# ps2_atmega32__board_with_connector_shogi.net
KiCad netlist of a schematic drawn in EAGLE
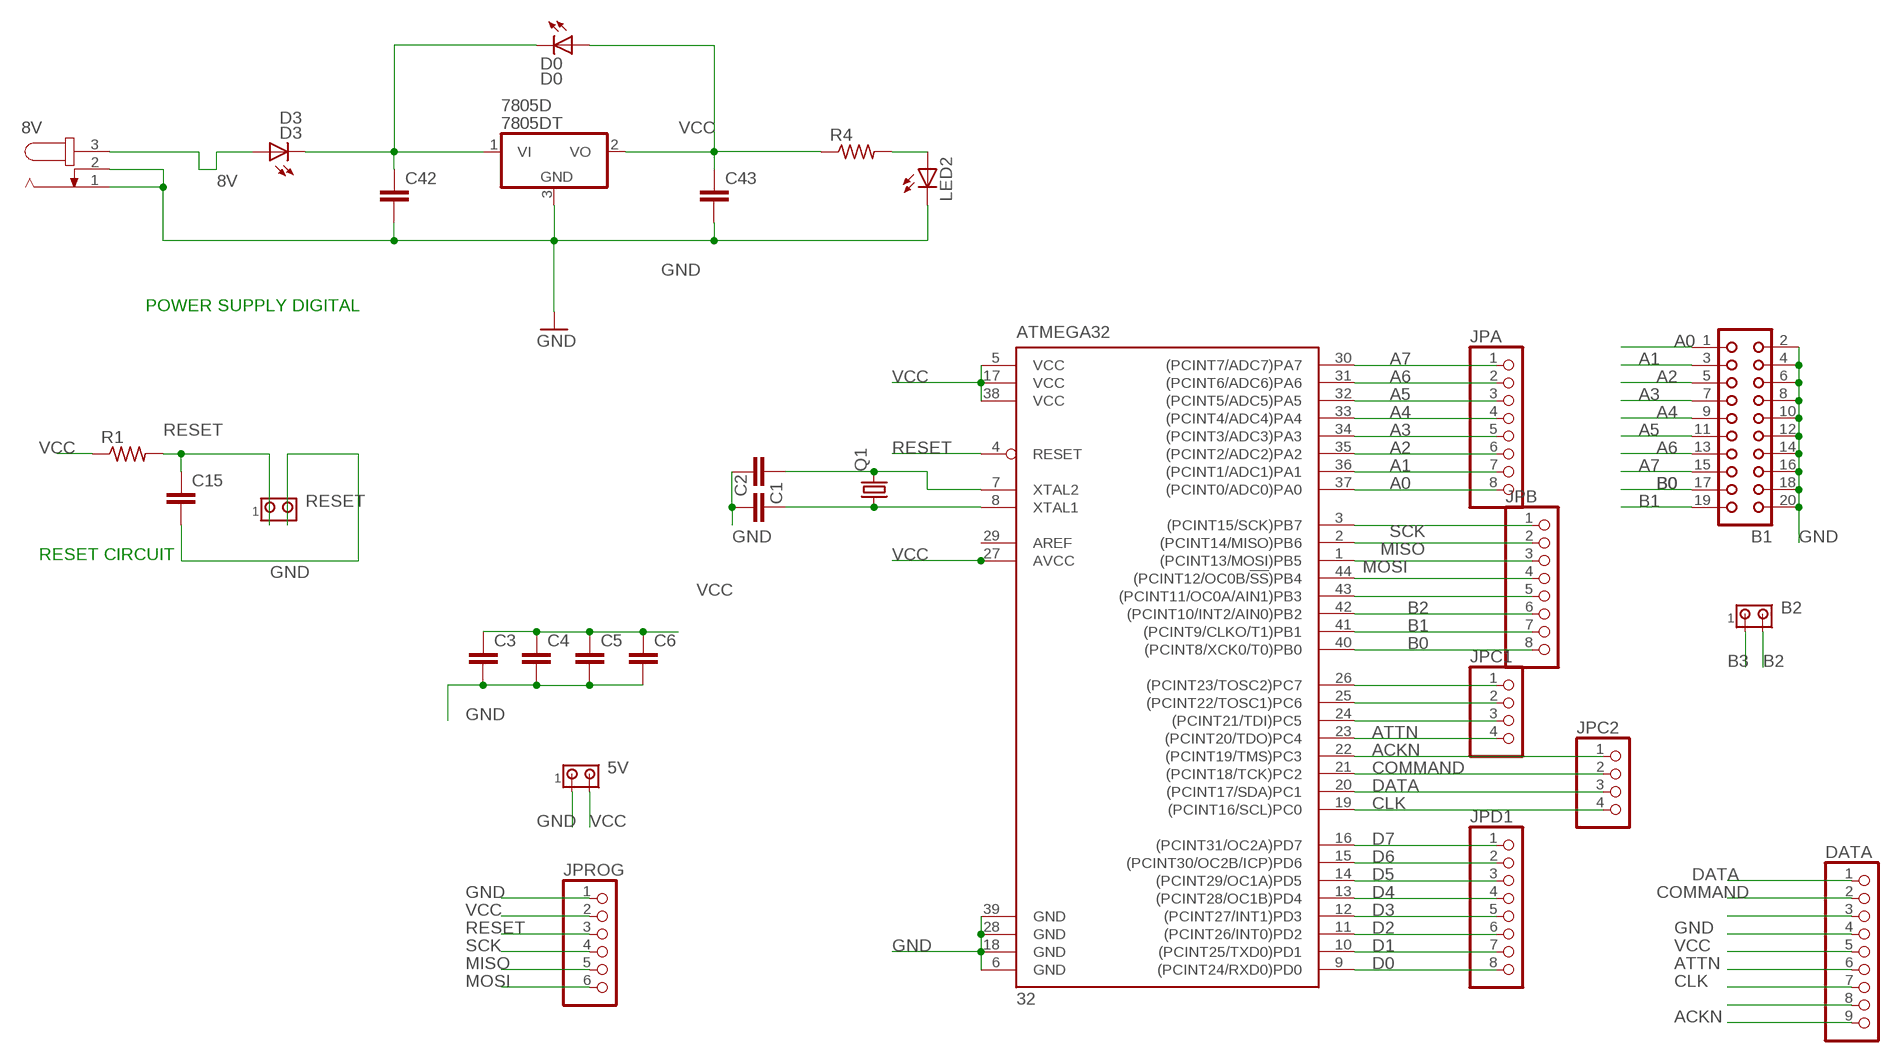
[diagram p0: schematic, sheet 1]

(export (version "E")
  (design (tool "Eeschema 10.0.6"))
  (components
    (comp (ref "5V")
      (value "MTA02-100")
      (footprint "eagle-import:10X02MTA")
      (libsource (lib "eagle-import") (part "MTA02-100"))
    )
    (comp (ref "8V")
      (value "JACK-PLUG0")
      (footprint "eagle-import:SPC4077")
      (libsource (lib "eagle-import") (part "JACK-PLUG0"))
    )
    (comp (ref "7805D")
      (value "7805DT")
      (footprint "eagle-import:TO252")
      (libsource (lib "eagle-import") (part "78DT05"))
    )
    (comp (ref "ATMEGA32")
      (value "32")
      (footprint "eagle-import:TQFP44")
      (libsource (lib "eagle-import") (part "ATMEGA644A"))
    )
    (comp (ref "B1")
      (value "CON20L")
      (footprint "eagle-import:CON20L")
      (libsource (lib "eagle-import") (part "CON20L"))
    )
    (comp (ref "B2")
      (value "MTA02-100")
      (footprint "eagle-import:10X02MTA")
      (libsource (lib "eagle-import") (part "MTA02-100"))
    )
    (comp (ref "C1")
      (value "C-EUC0603K")
      (footprint "eagle-import:C0603K")
      (libsource (lib "eagle-import") (part "C-EUC0603K"))
    )
    (comp (ref "C2")
      (value "C-EUC0603K")
      (footprint "eagle-import:C0603K")
      (libsource (lib "eagle-import") (part "C-EUC0603K"))
    )
    (comp (ref "C3")
      (value "C-EUC0603K")
      (footprint "eagle-import:C0603K")
      (libsource (lib "eagle-import") (part "C-EUC0603K"))
    )
    (comp (ref "C4")
      (value "C-EUC0603K")
      (footprint "eagle-import:C0603K")
      (libsource (lib "eagle-import") (part "C-EUC0603K"))
    )
    (comp (ref "C5")
      (value "C-EUC0603K")
      (footprint "eagle-import:C0603K")
      (libsource (lib "eagle-import") (part "C-EUC0603K"))
    )
    (comp (ref "C6")
      (value "C-EUC0603K")
      (footprint "eagle-import:C0603K")
      (libsource (lib "eagle-import") (part "C-EUC0603K"))
    )
    (comp (ref "C15")
      (value "C-EUC0603")
      (footprint "eagle-import:C0603")
      (libsource (lib "eagle-import") (part "C-EUC0603"))
    )
    (comp (ref "C42")
      (value "C-EUC0603")
      (footprint "eagle-import:C0603")
      (libsource (lib "eagle-import") (part "C-EUC0603"))
    )
    (comp (ref "C43")
      (value "C-EUC0603")
      (footprint "eagle-import:C0603")
      (libsource (lib "eagle-import") (part "C-EUC0603"))
    )
    (comp (ref "D0")
      (value "D0")
      (footprint "eagle-import:CHIPLED_1206")
      (libsource (lib "eagle-import") (part "LEDCHIPLED_1206"))
    )
    (comp (ref "D3")
      (value "D3")
      (footprint "eagle-import:CHIPLED_1206")
      (libsource (lib "eagle-import") (part "LEDCHIPLED_1206"))
    )
    (comp (ref "DATA")
      (value "PINHD-1X9")
      (footprint "eagle-import:1X09")
      (libsource (lib "eagle-import") (part "PINHD-1X9"))
    )
    (comp (ref "JPA")
      (value "PINHD-1X8")
      (footprint "eagle-import:1X08")
      (libsource (lib "eagle-import") (part "PINHD-1X8"))
    )
    (comp (ref "JPB")
      (value "PINHD-1X8")
      (footprint "eagle-import:1X08")
      (libsource (lib "eagle-import") (part "PINHD-1X8"))
    )
    (comp (ref "JPC1")
      (value "PINHD-1X4")
      (footprint "eagle-import:1X04")
      (libsource (lib "eagle-import") (part "PINHD-1X4"))
    )
    (comp (ref "JPC2")
      (value "PINHD-1X4")
      (footprint "eagle-import:1X04")
      (libsource (lib "eagle-import") (part "PINHD-1X4"))
    )
    (comp (ref "JPD1")
      (value "PINHD-1X8")
      (footprint "eagle-import:1X08")
      (libsource (lib "eagle-import") (part "PINHD-1X8"))
    )
    (comp (ref "JPROG")
      (value "PINHD-1X6")
      (footprint "eagle-import:1X06")
      (libsource (lib "eagle-import") (part "PINHD-1X6"))
    )
    (comp (ref "LED2")
      (value "LEDCHIPLED_1206")
      (footprint "eagle-import:CHIPLED_1206")
      (libsource (lib "eagle-import") (part "LEDCHIPLED_1206"))
    )
    (comp (ref "Q1")
      (value "CRYSTALHC49S")
      (footprint "eagle-import:HC49_S")
      (libsource (lib "eagle-import") (part "CRYSTALHC49S"))
    )
    (comp (ref "R1")
      (value "R-US_R0603")
      (footprint "eagle-import:R0603")
      (libsource (lib "eagle-import") (part "R-US_R0603"))
    )
    (comp (ref "R4")
      (value "R-US_R0603")
      (footprint "eagle-import:R0603")
      (libsource (lib "eagle-import") (part "R-US_R0603"))
    )
    (comp (ref "RESET")
      (value "MTA02-100")
      (footprint "eagle-import:10X02MTA")
      (libsource (lib "eagle-import") (part "MTA02-100"))
    )
  )
  (nets
    (net (code "1") (name "/8V") (class "Default")
      (node (ref "8V") (pin "3") (pinfunction "3_3") (pintype "passive"))
      (node (ref "D3") (pin "A") (pinfunction "A_A") (pintype "passive"))
    )
    (net (code "2") (name "/A0") (class "Default")
      (node (ref "ATMEGA32") (pin "37") (pinfunction "(PCINT0/ADC0)PA0_37") (pintype "bidirectional"))
      (node (ref "B1") (pin "1") (pinfunction "1_1") (pintype "passive"))
      (node (ref "JPA") (pin "8") (pinfunction "8_8") (pintype "passive"))
    )
    (net (code "3") (name "/A1") (class "Default")
      (node (ref "ATMEGA32") (pin "36") (pinfunction "(PCINT1/ADC1)PA1_36") (pintype "bidirectional"))
      (node (ref "B1") (pin "3") (pinfunction "3_3") (pintype "passive"))
      (node (ref "JPA") (pin "7") (pinfunction "7_7") (pintype "passive"))
    )
    (net (code "4") (name "/A2") (class "Default")
      (node (ref "ATMEGA32") (pin "35") (pinfunction "(PCINT2/ADC2)PA2_35") (pintype "bidirectional"))
      (node (ref "B1") (pin "5") (pinfunction "5_5") (pintype "passive"))
      (node (ref "JPA") (pin "6") (pinfunction "6_6") (pintype "passive"))
    )
    (net (code "5") (name "/A3") (class "Default")
      (node (ref "ATMEGA32") (pin "34") (pinfunction "(PCINT3/ADC3)PA3_34") (pintype "bidirectional"))
      (node (ref "B1") (pin "7") (pinfunction "7_7") (pintype "passive"))
      (node (ref "JPA") (pin "5") (pinfunction "5_5") (pintype "passive"))
    )
    (net (code "6") (name "/A4") (class "Default")
      (node (ref "ATMEGA32") (pin "33") (pinfunction "(PCINT4/ADC4)PA4_33") (pintype "bidirectional"))
      (node (ref "B1") (pin "9") (pinfunction "9_9") (pintype "passive"))
      (node (ref "JPA") (pin "4") (pinfunction "4_4") (pintype "passive"))
    )
    (net (code "7") (name "/A5") (class "Default")
      (node (ref "ATMEGA32") (pin "32") (pinfunction "(PCINT5/ADC5)PA5_32") (pintype "bidirectional"))
      (node (ref "B1") (pin "11") (pinfunction "11_11") (pintype "passive"))
      (node (ref "JPA") (pin "3") (pinfunction "3_3") (pintype "passive"))
    )
    (net (code "8") (name "/A6") (class "Default")
      (node (ref "ATMEGA32") (pin "31") (pinfunction "(PCINT6/ADC6)PA6_31") (pintype "bidirectional"))
      (node (ref "B1") (pin "13") (pinfunction "13_13") (pintype "passive"))
      (node (ref "JPA") (pin "2") (pinfunction "2_2") (pintype "passive"))
    )
    (net (code "9") (name "/A7") (class "Default")
      (node (ref "ATMEGA32") (pin "30") (pinfunction "(PCINT7/ADC7)PA7_30") (pintype "bidirectional"))
      (node (ref "B1") (pin "15") (pinfunction "15_15") (pintype "passive"))
      (node (ref "JPA") (pin "1") (pinfunction "1_1") (pintype "passive"))
    )
    (net (code "10") (name "/ACKN") (class "Default")
      (node (ref "ATMEGA32") (pin "22") (pinfunction "(PCINT19/TMS)PC3_22") (pintype "output"))
      (node (ref "DATA") (pin "9") (pinfunction "9_9") (pintype "passive"))
      (node (ref "JPC2") (pin "1") (pinfunction "1_1") (pintype "passive"))
    )
    (net (code "11") (name "/ATTN") (class "Default")
      (node (ref "ATMEGA32") (pin "23") (pinfunction "(PCINT20/TDO)PC4_23") (pintype "output"))
      (node (ref "DATA") (pin "6") (pinfunction "6_6") (pintype "passive"))
      (node (ref "JPC1") (pin "4") (pinfunction "4_4") (pintype "passive"))
    )
    (net (code "12") (name "/B0") (class "Default")
      (node (ref "ATMEGA32") (pin "40") (pinfunction "(PCINT8/XCK0/T0)PB0_40") (pintype "bidirectional"))
      (node (ref "B1") (pin "17") (pinfunction "17_17") (pintype "passive"))
      (node (ref "JPB") (pin "8") (pinfunction "8_8") (pintype "passive"))
    )
    (net (code "13") (name "/B1") (class "Default")
      (node (ref "ATMEGA32") (pin "41") (pinfunction "(PCINT9/CLKO/T1)PB1_41") (pintype "bidirectional"))
      (node (ref "B1") (pin "19") (pinfunction "19_19") (pintype "passive"))
      (node (ref "JPB") (pin "7") (pinfunction "7_7") (pintype "passive"))
    )
    (net (code "14") (name "/B2") (class "Default")
      (node (ref "ATMEGA32") (pin "42") (pinfunction "(PCINT10/INT2/AIN0)PB2_42") (pintype "bidirectional"))
      (node (ref "B2") (pin "2") (pinfunction "2_2") (pintype "passive"))
      (node (ref "JPB") (pin "6") (pinfunction "6_6") (pintype "passive"))
    )
    (net (code "15") (name "/B3") (class "Default")
      (node (ref "ATMEGA32") (pin "43") (pinfunction "(PCINT11/OC0A/AIN1)PB3_43") (pintype "bidirectional"))
      (node (ref "B2") (pin "1") (pinfunction "1_1") (pintype "passive"))
      (node (ref "JPB") (pin "5") (pinfunction "5_5") (pintype "passive"))
    )
    (net (code "16") (name "/CLK") (class "Default")
      (node (ref "ATMEGA32") (pin "19") (pinfunction "(PCINT16/SCL)PC0_19") (pintype "output"))
      (node (ref "DATA") (pin "7") (pinfunction "7_7") (pintype "passive"))
      (node (ref "JPC2") (pin "4") (pinfunction "4_4") (pintype "passive"))
    )
    (net (code "17") (name "/COMMAND") (class "Default")
      (node (ref "ATMEGA32") (pin "21") (pinfunction "(PCINT18/TCK)PC2_21") (pintype "output"))
      (node (ref "DATA") (pin "2") (pinfunction "2_2") (pintype "passive"))
      (node (ref "JPC2") (pin "2") (pinfunction "2_2") (pintype "passive"))
    )
    (net (code "18") (name "/D0") (class "Default")
      (node (ref "ATMEGA32") (pin "9") (pinfunction "(PCINT24/RXD0)PD0_9") (pintype "bidirectional"))
      (node (ref "JPD1") (pin "8") (pinfunction "8_8") (pintype "passive"))
    )
    (net (code "19") (name "/D1") (class "Default")
      (node (ref "ATMEGA32") (pin "10") (pinfunction "(PCINT25/TXD0)PD1_10") (pintype "bidirectional"))
      (node (ref "JPD1") (pin "7") (pinfunction "7_7") (pintype "passive"))
    )
    (net (code "20") (name "/D2") (class "Default")
      (node (ref "ATMEGA32") (pin "11") (pinfunction "(PCINT26/INT0)PD2_11") (pintype "bidirectional"))
      (node (ref "JPD1") (pin "6") (pinfunction "6_6") (pintype "passive"))
    )
    (net (code "21") (name "/D3") (class "Default")
      (node (ref "ATMEGA32") (pin "12") (pinfunction "(PCINT27/INT1)PD3_12") (pintype "bidirectional"))
      (node (ref "JPD1") (pin "5") (pinfunction "5_5") (pintype "passive"))
    )
    (net (code "22") (name "/D4") (class "Default")
      (node (ref "ATMEGA32") (pin "13") (pinfunction "(PCINT28/OC1B)PD4_13") (pintype "bidirectional"))
      (node (ref "JPD1") (pin "4") (pinfunction "4_4") (pintype "passive"))
    )
    (net (code "23") (name "/D5") (class "Default")
      (node (ref "ATMEGA32") (pin "14") (pinfunction "(PCINT29/OC1A)PD5_14") (pintype "bidirectional"))
      (node (ref "JPD1") (pin "3") (pinfunction "3_3") (pintype "passive"))
    )
    (net (code "24") (name "/D6") (class "Default")
      (node (ref "ATMEGA32") (pin "15") (pinfunction "(PCINT30/OC2B/ICP)PD6_15") (pintype "bidirectional"))
      (node (ref "JPD1") (pin "2") (pinfunction "2_2") (pintype "passive"))
    )
    (net (code "25") (name "/D7") (class "Default")
      (node (ref "ATMEGA32") (pin "16") (pinfunction "(PCINT31/OC2A)PD7_16") (pintype "bidirectional"))
      (node (ref "JPD1") (pin "1") (pinfunction "1_1") (pintype "passive"))
    )
    (net (code "26") (name "/DATA") (class "Default")
      (node (ref "ATMEGA32") (pin "20") (pinfunction "(PCINT17/SDA)PC1_20") (pintype "output"))
      (node (ref "DATA") (pin "1") (pinfunction "1_1") (pintype "passive"))
      (node (ref "JPC2") (pin "3") (pinfunction "3_3") (pintype "passive"))
    )
    (net (code "27") (name "/MISO") (class "Default")
      (node (ref "ATMEGA32") (pin "2") (pinfunction "(PCINT14/MISO)PB6_2") (pintype "bidirectional"))
      (node (ref "JPB") (pin "2") (pinfunction "2_2") (pintype "passive"))
      (node (ref "JPROG") (pin "5") (pinfunction "5_5") (pintype "passive"))
    )
    (net (code "28") (name "/MOSI") (class "Default")
      (node (ref "ATMEGA32") (pin "1") (pinfunction "(PCINT13/MOSI)PB5_1") (pintype "bidirectional"))
      (node (ref "JPB") (pin "3") (pinfunction "3_3") (pintype "passive"))
      (node (ref "JPROG") (pin "6") (pinfunction "6_6") (pintype "passive"))
    )
    (net (code "29") (name "/RESET") (class "Default")
      (node (ref "ATMEGA32") (pin "4") (pinfunction "RESET_4") (pintype "input"))
      (node (ref "C15") (pin "1") (pinfunction "1_1") (pintype "passive"))
      (node (ref "JPROG") (pin "3") (pinfunction "3_3") (pintype "passive"))
      (node (ref "R1") (pin "2") (pinfunction "2_2") (pintype "passive"))
      (node (ref "RESET") (pin "1") (pinfunction "1_1") (pintype "passive"))
    )
    (net (code "30") (name "/SCK") (class "Default")
      (node (ref "ATMEGA32") (pin "3") (pinfunction "(PCINT15/SCK)PB7_3") (pintype "bidirectional"))
      (node (ref "JPB") (pin "1") (pinfunction "1_1") (pintype "passive"))
      (node (ref "JPROG") (pin "4") (pinfunction "4_4") (pintype "passive"))
    )
    (net (code "31") (name "/VCC") (class "Default")
      (node (ref "5V") (pin "2") (pinfunction "2_2") (pintype "passive"))
      (node (ref "7805D") (pin "2") (pinfunction "VO_2") (pintype "passive"))
      (node (ref "ATMEGA32") (pin "17") (pinfunction "VCC_17") (pintype "power_in"))
      (node (ref "ATMEGA32") (pin "27") (pinfunction "AVCC_27") (pintype "power_in"))
      (node (ref "ATMEGA32") (pin "38") (pinfunction "VCC_38") (pintype "power_in"))
      (node (ref "ATMEGA32") (pin "5") (pinfunction "VCC_5") (pintype "power_in"))
      (node (ref "C3") (pin "1") (pinfunction "1_1") (pintype "passive"))
      (node (ref "C4") (pin "1") (pinfunction "1_1") (pintype "passive"))
      (node (ref "C43") (pin "1") (pinfunction "1_1") (pintype "passive"))
      (node (ref "C5") (pin "1") (pinfunction "1_1") (pintype "passive"))
      (node (ref "C6") (pin "1") (pinfunction "1_1") (pintype "passive"))
      (node (ref "D0") (pin "A") (pinfunction "A_A") (pintype "passive"))
      (node (ref "DATA") (pin "5") (pinfunction "5_5") (pintype "passive"))
      (node (ref "JPROG") (pin "2") (pinfunction "2_2") (pintype "passive"))
      (node (ref "R1") (pin "1") (pinfunction "1_1") (pintype "passive"))
      (node (ref "R4") (pin "1") (pinfunction "1_1") (pintype "passive"))
    )
    (net (code "32") (name "GND") (class "Default")
      (node (ref "5V") (pin "1") (pinfunction "1_1") (pintype "passive"))
      (node (ref "7805D") (pin "3") (pinfunction "GND_3") (pintype "passive"))
      (node (ref "8V") (pin "1") (pinfunction "1_1") (pintype "passive"))
      (node (ref "8V") (pin "2") (pinfunction "2_2") (pintype "passive"))
      (node (ref "ATMEGA32") (pin "18") (pinfunction "GND_18") (pintype "power_in"))
      (node (ref "ATMEGA32") (pin "28") (pinfunction "GND_28") (pintype "power_in"))
      (node (ref "ATMEGA32") (pin "39") (pinfunction "GND_39") (pintype "power_in"))
      (node (ref "ATMEGA32") (pin "6") (pinfunction "GND_6") (pintype "power_in"))
      (node (ref "B1") (pin "10") (pinfunction "10_10") (pintype "passive"))
      (node (ref "B1") (pin "12") (pinfunction "12_12") (pintype "passive"))
      (node (ref "B1") (pin "14") (pinfunction "14_14") (pintype "passive"))
      (node (ref "B1") (pin "16") (pinfunction "16_16") (pintype "passive"))
      (node (ref "B1") (pin "18") (pinfunction "18_18") (pintype "passive"))
      (node (ref "B1") (pin "2") (pinfunction "2_2") (pintype "passive"))
      (node (ref "B1") (pin "20") (pinfunction "20_20") (pintype "passive"))
      (node (ref "B1") (pin "4") (pinfunction "4_4") (pintype "passive"))
      (node (ref "B1") (pin "6") (pinfunction "6_6") (pintype "passive"))
      (node (ref "B1") (pin "8") (pinfunction "8_8") (pintype "passive"))
      (node (ref "C1") (pin "2") (pinfunction "2_2") (pintype "passive"))
      (node (ref "C15") (pin "2") (pinfunction "2_2") (pintype "passive"))
      (node (ref "C2") (pin "1") (pinfunction "1_1") (pintype "passive"))
      (node (ref "C3") (pin "2") (pinfunction "2_2") (pintype "passive"))
      (node (ref "C4") (pin "2") (pinfunction "2_2") (pintype "passive"))
      (node (ref "C42") (pin "2") (pinfunction "2_2") (pintype "passive"))
      (node (ref "C43") (pin "2") (pinfunction "2_2") (pintype "passive"))
      (node (ref "C5") (pin "2") (pinfunction "2_2") (pintype "passive"))
      (node (ref "C6") (pin "2") (pinfunction "2_2") (pintype "passive"))
      (node (ref "DATA") (pin "4") (pinfunction "4_4") (pintype "passive"))
      (node (ref "JPROG") (pin "1") (pinfunction "1_1") (pintype "passive"))
      (node (ref "LED2") (pin "C") (pinfunction "C_C") (pintype "passive"))
      (node (ref "RESET") (pin "2") (pinfunction "2_2") (pintype "passive"))
    )
    (net (code "33") (name "Net-(7805D-VI)") (class "Default")
      (node (ref "7805D") (pin "1") (pinfunction "VI_1") (pintype "input"))
      (node (ref "C42") (pin "1") (pinfunction "1_1") (pintype "passive"))
      (node (ref "D0") (pin "C") (pinfunction "C_C") (pintype "passive"))
      (node (ref "D3") (pin "C") (pinfunction "C_C") (pintype "passive"))
    )
    (net (code "34") (name "Net-(ATMEGA32-(PCINT12{slash}OC0B{slash}~{SS})PB4)") (class "Default")
      (node (ref "ATMEGA32") (pin "44") (pinfunction "(PCINT12/OC0B/~{SS})PB4_44") (pintype "bidirectional"))
      (node (ref "JPB") (pin "4") (pinfunction "4_4") (pintype "passive"))
    )
    (net (code "35") (name "Net-(ATMEGA32-(PCINT21{slash}TDI)PC5)") (class "Default")
      (node (ref "ATMEGA32") (pin "24") (pinfunction "(PCINT21/TDI)PC5_24") (pintype "output"))
      (node (ref "JPC1") (pin "3") (pinfunction "3_3") (pintype "passive"))
    )
    (net (code "36") (name "Net-(ATMEGA32-(PCINT22{slash}TOSC1)PC6)") (class "Default")
      (node (ref "ATMEGA32") (pin "25") (pinfunction "(PCINT22/TOSC1)PC6_25") (pintype "output"))
      (node (ref "JPC1") (pin "2") (pinfunction "2_2") (pintype "passive"))
    )
    (net (code "37") (name "Net-(ATMEGA32-(PCINT23{slash}TOSC2)PC7)") (class "Default")
      (node (ref "ATMEGA32") (pin "26") (pinfunction "(PCINT23/TOSC2)PC7_26") (pintype "output"))
      (node (ref "JPC1") (pin "1") (pinfunction "1_1") (pintype "passive"))
    )
    (net (code "38") (name "Net-(ATMEGA32-XTAL1)") (class "Default")
      (node (ref "ATMEGA32") (pin "8") (pinfunction "XTAL1_8") (pintype "bidirectional"))
      (node (ref "C2") (pin "2") (pinfunction "2_2") (pintype "passive"))
      (node (ref "Q1") (pin "1") (pinfunction "1_1") (pintype "passive"))
    )
    (net (code "39") (name "Net-(ATMEGA32-XTAL2)") (class "Default")
      (node (ref "ATMEGA32") (pin "7") (pinfunction "XTAL2_7") (pintype "bidirectional"))
      (node (ref "C1") (pin "1") (pinfunction "1_1") (pintype "passive"))
      (node (ref "Q1") (pin "2") (pinfunction "2_2") (pintype "passive"))
    )
    (net (code "40") (name "Net-(LED2-PadA)") (class "Default")
      (node (ref "LED2") (pin "A") (pinfunction "A_A") (pintype "passive"))
      (node (ref "R4") (pin "2") (pinfunction "2_2") (pintype "passive"))
    )
    (net (code "41") (name "unconnected-(ATMEGA32-AREF-Pad29)") (class "Default")
      (node (ref "ATMEGA32") (pin "29") (pinfunction "AREF_29") (pintype "passive"))
    )
    (net (code "42") (name "unconnected-(DATA-Pad3)") (class "Default")
      (node (ref "DATA") (pin "3") (pinfunction "3_3") (pintype "passive"))
    )
    (net (code "43") (name "unconnected-(DATA-Pad8)") (class "Default")
      (node (ref "DATA") (pin "8") (pinfunction "8_8") (pintype "passive"))
    )
  )
)
